# modbrainsv0_4_1.net
KiCad netlist of a schematic drawn in EAGLE
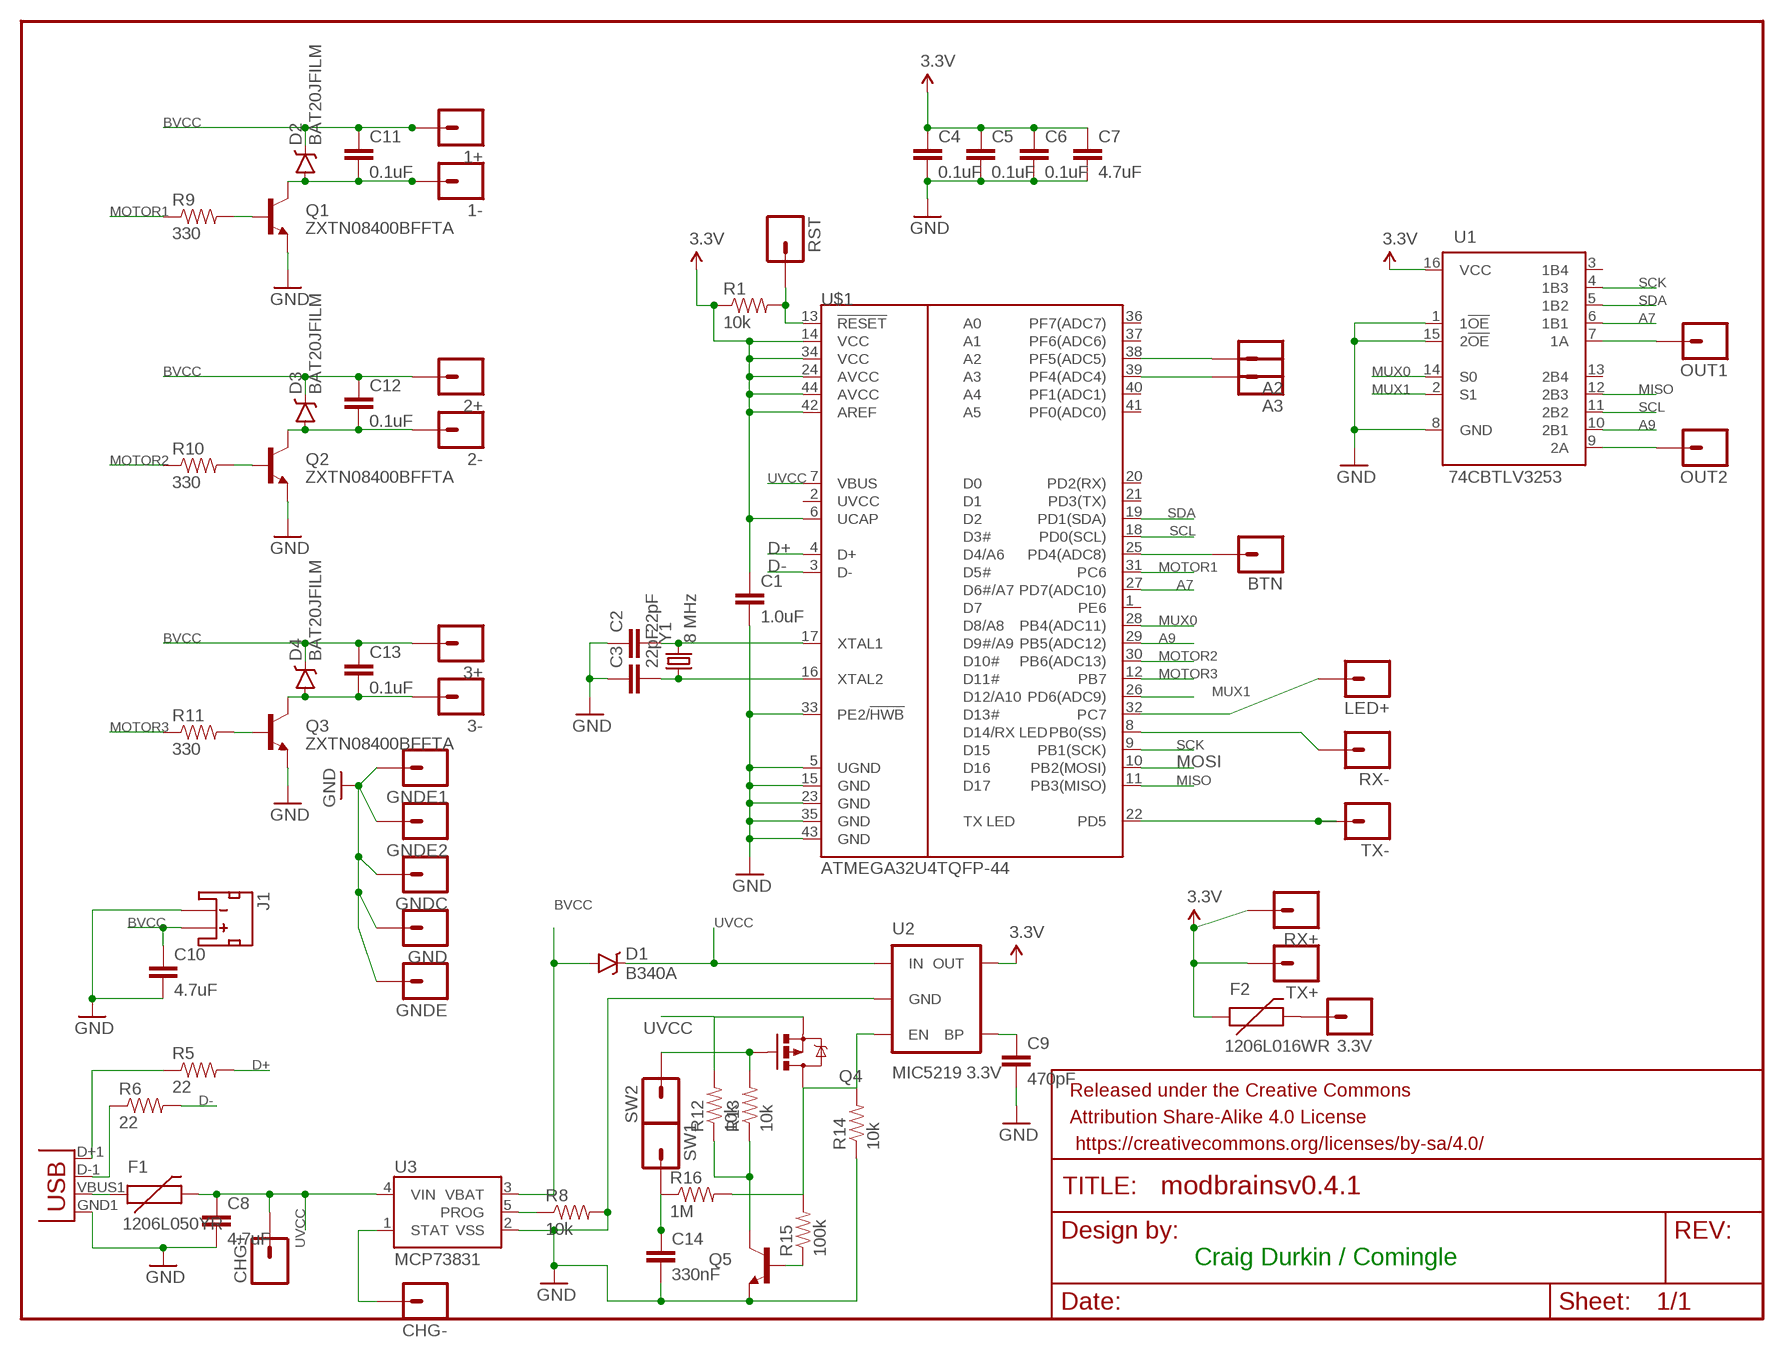
[diagram p0: schematic, sheet 1]

(export (version "E")
  (design (tool "Eeschema 10.0.6"))
  (components
    (comp (ref "1+")
      (value "M01PTH")
      (footprint "eagle-import:1X01")
      (libsource (lib "eagle-import") (part "M01PTH"))
    )
    (comp (ref "1-")
      (value "M01PTH")
      (footprint "eagle-import:1X01")
      (libsource (lib "eagle-import") (part "M01PTH"))
    )
    (comp (ref "2+")
      (value "M01PTH")
      (footprint "eagle-import:1X01")
      (libsource (lib "eagle-import") (part "M01PTH"))
    )
    (comp (ref "2-")
      (value "M01PTH")
      (footprint "eagle-import:1X01")
      (libsource (lib "eagle-import") (part "M01PTH"))
    )
    (comp (ref "3+")
      (value "M01PTH")
      (footprint "eagle-import:1X01")
      (libsource (lib "eagle-import") (part "M01PTH"))
    )
    (comp (ref "3-")
      (value "M01PTH")
      (footprint "eagle-import:1X01")
      (libsource (lib "eagle-import") (part "M01PTH"))
    )
    (comp (ref "3.3V")
      (value "M01PTH")
      (footprint "eagle-import:1X01")
      (libsource (lib "eagle-import") (part "M01PTH"))
    )
    (comp (ref "A2")
      (value "M01PTH")
      (footprint "eagle-import:1X01")
      (libsource (lib "eagle-import") (part "M01PTH"))
    )
    (comp (ref "A3")
      (value "M01PTH")
      (footprint "eagle-import:1X01")
      (libsource (lib "eagle-import") (part "M01PTH"))
    )
    (comp (ref "BTN")
      (value "M01PTH")
      (footprint "eagle-import:1X01")
      (libsource (lib "eagle-import") (part "M01PTH"))
    )
    (comp (ref "C1")
      (value "1.0uF")
      (footprint "eagle-import:0603-CAP")
      (libsource (lib "eagle-import") (part "CAP0603-CAP"))
    )
    (comp (ref "C2")
      (value "22pF")
      (footprint "eagle-import:0603-CAP")
      (libsource (lib "eagle-import") (part "CAP0603-CAP"))
    )
    (comp (ref "C3")
      (value "22pF")
      (footprint "eagle-import:0603-CAP")
      (libsource (lib "eagle-import") (part "CAP0603-CAP"))
    )
    (comp (ref "C4")
      (value "0.1uF")
      (footprint "eagle-import:0603-CAP")
      (libsource (lib "eagle-import") (part "SparkFun-Passives_CAP0603-CAP"))
    )
    (comp (ref "C5")
      (value "0.1uF")
      (footprint "eagle-import:0603-CAP")
      (libsource (lib "eagle-import") (part "SparkFun-Passives_CAP0603-CAP"))
    )
    (comp (ref "C6")
      (value "0.1uF")
      (footprint "eagle-import:0603-CAP")
      (libsource (lib "eagle-import") (part "SparkFun-Passives_CAP0603-CAP"))
    )
    (comp (ref "C7")
      (value "4.7uF")
      (footprint "eagle-import:0603-CAP")
      (libsource (lib "eagle-import") (part "SparkFun-Passives_CAP0603-CAP"))
    )
    (comp (ref "C8")
      (value "4.7uF")
      (footprint "eagle-import:1206")
      (libsource (lib "eagle-import") (part "SparkFun-Passives_CAP1206"))
    )
    (comp (ref "C9")
      (value "470pF")
      (footprint "eagle-import:0603-CAP")
      (libsource (lib "eagle-import") (part "CAP0603-CAP"))
    )
    (comp (ref "C10")
      (value "4.7uF")
      (footprint "eagle-import:1206")
      (libsource (lib "eagle-import") (part "SparkFun-Passives_CAP1206"))
    )
    (comp (ref "C11")
      (value "0.1uF")
      (footprint "eagle-import:0603-CAP")
      (libsource (lib "eagle-import") (part "CAP0603-CAP"))
    )
    (comp (ref "C12")
      (value "0.1uF")
      (footprint "eagle-import:0603-CAP")
      (libsource (lib "eagle-import") (part "CAP0603-CAP"))
    )
    (comp (ref "C13")
      (value "0.1uF")
      (footprint "eagle-import:0603-CAP")
      (libsource (lib "eagle-import") (part "CAP0603-CAP"))
    )
    (comp (ref "C14")
      (value "330nF")
      (footprint "eagle-import:0603-CAP")
      (libsource (lib "eagle-import") (part "CAP0603-CAP"))
    )
    (comp (ref "CHG+")
      (value "M01PTH")
      (footprint "eagle-import:1X01")
      (libsource (lib "eagle-import") (part "M01PTH"))
    )
    (comp (ref "CHG-")
      (value "M01PTH")
      (footprint "eagle-import:1X01")
      (libsource (lib "eagle-import") (part "M01PTH"))
    )
    (comp (ref "D1")
      (value "B340A")
      (footprint "eagle-import:SMA-DIODE")
      (libsource (lib "eagle-import") (part "DIODE-SCHOTTKY-B340A"))
    )
    (comp (ref "D2")
      (value "BAT20JFILM")
      (footprint "eagle-import:SOD-323")
      (libsource (lib "eagle-import") (part "BAT20JFILM"))
    )
    (comp (ref "D3")
      (value "BAT20JFILM")
      (footprint "eagle-import:SOD-323")
      (libsource (lib "eagle-import") (part "BAT20JFILM"))
    )
    (comp (ref "D4")
      (value "BAT20JFILM")
      (footprint "eagle-import:SOD-323")
      (libsource (lib "eagle-import") (part "BAT20JFILM"))
    )
    (comp (ref "F1")
      (value "1206L050YR")
      (footprint "eagle-import:PTC-1206")
      (libsource (lib "eagle-import") (part "PTCSMD"))
    )
    (comp (ref "F2")
      (value "1206L016WR")
      (footprint "eagle-import:PTC-1206")
      (libsource (lib "eagle-import") (part "PTCSMD"))
    )
    (comp (ref "FRAME1")
      (value "FRAME-LETTER")
      (footprint "eagle-import:CREATIVE_COMMONS")
      (libsource (lib "eagle-import") (part "FRAME-LETTER"))
    )
    (comp (ref "GND")
      (value "M01PTH")
      (footprint "eagle-import:1X01")
      (libsource (lib "eagle-import") (part "M01PTH"))
    )
    (comp (ref "GNDC")
      (value "M01PTH")
      (footprint "eagle-import:1X01")
      (libsource (lib "eagle-import") (part "M01PTH"))
    )
    (comp (ref "GNDE")
      (value "M01PTH")
      (footprint "eagle-import:1X01")
      (libsource (lib "eagle-import") (part "M01PTH"))
    )
    (comp (ref "GNDE1")
      (value "M01PTH")
      (footprint "eagle-import:1X01")
      (libsource (lib "eagle-import") (part "M01PTH"))
    )
    (comp (ref "GNDE2")
      (value "M01PTH")
      (footprint "eagle-import:1X01")
      (libsource (lib "eagle-import") (part "M01PTH"))
    )
    (comp (ref "J1")
      (value "JST_2MM_MALE")
      (footprint "eagle-import:JST-2-SMD")
      (libsource (lib "eagle-import") (part "JST_2MM_MALE"))
    )
    (comp (ref "JP4")
      (value "USB")
      (footprint "eagle-import:USB-B-MICRO-SMD_V03")
      (libsource (lib "eagle-import") (part "USB"))
    )
    (comp (ref "LED+")
      (value "M01PTH")
      (footprint "eagle-import:1X01")
      (libsource (lib "eagle-import") (part "M01PTH"))
    )
    (comp (ref "OUT1")
      (value "M01PTH")
      (footprint "eagle-import:1X01")
      (libsource (lib "eagle-import") (part "M01PTH"))
    )
    (comp (ref "OUT2")
      (value "M01PTH")
      (footprint "eagle-import:1X01")
      (libsource (lib "eagle-import") (part "M01PTH"))
    )
    (comp (ref "Q1")
      (value "ZXTN08400BFFTA")
      (footprint "eagle-import:SOT23-3")
      (libsource (lib "eagle-import") (part "TRANSISTOR_NPNSOT23-3"))
    )
    (comp (ref "Q2")
      (value "ZXTN08400BFFTA")
      (footprint "eagle-import:SOT23-3")
      (libsource (lib "eagle-import") (part "TRANSISTOR_NPNSOT23-3"))
    )
    (comp (ref "Q3")
      (value "ZXTN08400BFFTA")
      (footprint "eagle-import:SOT23-3")
      (libsource (lib "eagle-import") (part "TRANSISTOR_NPNSOT23-3"))
    )
    (comp (ref "Q4")
      (value "NTS2101PT1G")
      (footprint "eagle-import:SOT23-3")
      (libsource (lib "eagle-import") (part "MOSFET-PCHANNEL"))
    )
    (comp (ref "Q5")
      (value "MMBT2222A")
      (footprint "eagle-import:SOT23-3")
      (libsource (lib "eagle-import") (part "TRANSISTOR_NPNMMBT2222A"))
    )
    (comp (ref "R1")
      (value "10k")
      (footprint "eagle-import:0603-RES")
      (libsource (lib "eagle-import") (part "RESISTOR0603-RES"))
    )
    (comp (ref "R5")
      (value "22")
      (footprint "eagle-import:0603-RES")
      (libsource (lib "eagle-import") (part "RESISTOR0603-RES"))
    )
    (comp (ref "R6")
      (value "22")
      (footprint "eagle-import:0603-RES")
      (libsource (lib "eagle-import") (part "RESISTOR0603-RES"))
    )
    (comp (ref "R8")
      (value "10k")
      (footprint "eagle-import:0603-RES")
      (libsource (lib "eagle-import") (part "RESISTOR0603-RES"))
    )
    (comp (ref "R9")
      (value "330")
      (footprint "eagle-import:0603-RES")
      (libsource (lib "eagle-import") (part "RESISTOR0603-RES"))
    )
    (comp (ref "R10")
      (value "330")
      (footprint "eagle-import:0603-RES")
      (libsource (lib "eagle-import") (part "RESISTOR0603-RES"))
    )
    (comp (ref "R11")
      (value "330")
      (footprint "eagle-import:0603-RES")
      (libsource (lib "eagle-import") (part "RESISTOR0603-RES"))
    )
    (comp (ref "R12")
      (value "10k")
      (footprint "eagle-import:0603-RES")
      (libsource (lib "eagle-import") (part "RESISTOR0603-RES"))
    )
    (comp (ref "R13")
      (value "10k")
      (footprint "eagle-import:0603-RES")
      (libsource (lib "eagle-import") (part "RESISTOR0603-RES"))
    )
    (comp (ref "R14")
      (value "10k")
      (footprint "eagle-import:0603-RES")
      (libsource (lib "eagle-import") (part "RESISTOR0603-RES"))
    )
    (comp (ref "R15")
      (value "100k")
      (footprint "eagle-import:0603-RES")
      (libsource (lib "eagle-import") (part "RESISTOR0603-RES"))
    )
    (comp (ref "R16")
      (value "1M")
      (footprint "eagle-import:0603-RES")
      (libsource (lib "eagle-import") (part "RESISTOR0603-RES"))
    )
    (comp (ref "RST")
      (value "M01PTH")
      (footprint "eagle-import:1X01")
      (libsource (lib "eagle-import") (part "M01PTH"))
    )
    (comp (ref "RX+")
      (value "M01PTH")
      (footprint "eagle-import:1X01")
      (libsource (lib "eagle-import") (part "M01PTH"))
    )
    (comp (ref "RX-")
      (value "M01PTH")
      (footprint "eagle-import:1X01")
      (libsource (lib "eagle-import") (part "M01PTH"))
    )
    (comp (ref "SW1")
      (value "M01PTH")
      (footprint "eagle-import:1X01")
      (libsource (lib "eagle-import") (part "M01PTH"))
    )
    (comp (ref "SW2")
      (value "M01PTH")
      (footprint "eagle-import:1X01")
      (libsource (lib "eagle-import") (part "M01PTH"))
    )
    (comp (ref "TX+")
      (value "M01PTH")
      (footprint "eagle-import:1X01")
      (libsource (lib "eagle-import") (part "M01PTH"))
    )
    (comp (ref "TX-")
      (value "M01PTH")
      (footprint "eagle-import:1X01")
      (libsource (lib "eagle-import") (part "M01PTH"))
    )
    (comp (ref "U$1")
      (value "ATMEGA32U4TQFP-44")
      (footprint "eagle-import:TQFP44")
      (libsource (lib "eagle-import") (part "ATMEGA32U4TQFP-44"))
    )
    (comp (ref "U1")
      (value "74CBTLV3253")
      (footprint "eagle-import:SSOP16-PRACTICE")
      (libsource (lib "eagle-import") (part "74CBTLV3253"))
    )
    (comp (ref "U2")
      (value "MIC5219 3.3V")
      (footprint "eagle-import:SOT23-5")
      (libsource (lib "eagle-import") (part "V_REG_MIC52193.3V"))
    )
    (comp (ref "U3")
      (value "MCP73831")
      (footprint "eagle-import:SOT23-5")
      (libsource (lib "eagle-import") (part "MCP73831"))
    )
    (comp (ref "Y1")
      (value "8 MHz")
      (footprint "eagle-import:CRYSTAL-SMD-5X3")
      (libsource (lib "eagle-import") (part "CRYSTAL5X3"))
    )
  )
  (nets
    (net (code "1") (name "/A7") (class "Default")
      (node (ref "U$1") (pin "27") (pinfunction "PD7(ADC10)_27") (pintype "bidirectional"))
      (node (ref "U1") (pin "6") (pinfunction "1B1_6") (pintype "bidirectional"))
    )
    (net (code "2") (name "/A9") (class "Default")
      (node (ref "U$1") (pin "29") (pinfunction "PB5(ADC12)_29") (pintype "bidirectional"))
      (node (ref "U1") (pin "10") (pinfunction "2B1_10") (pintype "bidirectional"))
    )
    (net (code "3") (name "/BVCC") (class "Default")
      (node (ref "1+") (pin "1") (pinfunction "1_1") (pintype "passive"))
      (node (ref "2+") (pin "1") (pinfunction "1_1") (pintype "passive"))
      (node (ref "3+") (pin "1") (pinfunction "1_1") (pintype "passive"))
      (node (ref "C10") (pin "1") (pinfunction "1_1") (pintype "passive"))
      (node (ref "C11") (pin "1") (pinfunction "1_1") (pintype "passive"))
      (node (ref "C12") (pin "1") (pinfunction "1_1") (pintype "passive"))
      (node (ref "C13") (pin "1") (pinfunction "1_1") (pintype "passive"))
      (node (ref "D1") (pin "A") (pinfunction "A_A") (pintype "passive"))
      (node (ref "D2") (pin "C") (pinfunction "C_C") (pintype "passive"))
      (node (ref "D3") (pin "C") (pinfunction "C_C") (pintype "passive"))
      (node (ref "D4") (pin "C") (pinfunction "C_C") (pintype "passive"))
      (node (ref "J1") (pin "2") (pinfunction "+_2") (pintype "bidirectional"))
      (node (ref "U3") (pin "3") (pinfunction "VBAT_3") (pintype "power_in"))
    )
    (net (code "4") (name "/D+") (class "Default")
      (node (ref "R5") (pin "2") (pinfunction "2_2") (pintype "passive"))
      (node (ref "U$1") (pin "4") (pinfunction "D+_4") (pintype "bidirectional"))
    )
    (net (code "5") (name "/D-") (class "Default")
      (node (ref "R6") (pin "2") (pinfunction "2_2") (pintype "passive"))
      (node (ref "U$1") (pin "3") (pinfunction "D-_3") (pintype "bidirectional"))
    )
    (net (code "6") (name "/MISO") (class "Default")
      (node (ref "U$1") (pin "11") (pinfunction "PB3(MISO)_11") (pintype "bidirectional"))
      (node (ref "U1") (pin "12") (pinfunction "2B3_12") (pintype "bidirectional"))
    )
    (net (code "7") (name "/MOSI") (class "Default")
      (node (ref "U$1") (pin "10") (pinfunction "PB2(MOSI)_10") (pintype "bidirectional"))
    )
    (net (code "8") (name "/MOTOR1") (class "Default")
      (node (ref "R9") (pin "1") (pinfunction "1_1") (pintype "passive"))
      (node (ref "U$1") (pin "31") (pinfunction "PC6_31") (pintype "bidirectional"))
    )
    (net (code "9") (name "/MOTOR2") (class "Default")
      (node (ref "R10") (pin "1") (pinfunction "1_1") (pintype "passive"))
      (node (ref "U$1") (pin "30") (pinfunction "PB6(ADC13)_30") (pintype "bidirectional"))
    )
    (net (code "10") (name "/MOTOR3") (class "Default")
      (node (ref "R11") (pin "1") (pinfunction "1_1") (pintype "passive"))
      (node (ref "U$1") (pin "12") (pinfunction "PB7_12") (pintype "bidirectional"))
    )
    (net (code "11") (name "/MUX0") (class "Default")
      (node (ref "U$1") (pin "28") (pinfunction "PB4(ADC11)_28") (pintype "bidirectional"))
      (node (ref "U1") (pin "14") (pinfunction "S0_14") (pintype "bidirectional"))
    )
    (net (code "12") (name "/MUX1") (class "Default")
      (node (ref "U$1") (pin "26") (pinfunction "PD6(ADC9)_26") (pintype "bidirectional"))
      (node (ref "U1") (pin "2") (pinfunction "S1_2") (pintype "bidirectional"))
    )
    (net (code "13") (name "/SCK") (class "Default")
      (node (ref "U$1") (pin "9") (pinfunction "PB1(SCK)_9") (pintype "bidirectional"))
      (node (ref "U1") (pin "4") (pinfunction "1B3_4") (pintype "bidirectional"))
    )
    (net (code "14") (name "/SCL") (class "Default")
      (node (ref "U$1") (pin "18") (pinfunction "PD0(SCL)_18") (pintype "bidirectional"))
      (node (ref "U1") (pin "11") (pinfunction "2B2_11") (pintype "bidirectional"))
    )
    (net (code "15") (name "/SDA") (class "Default")
      (node (ref "U$1") (pin "19") (pinfunction "PD1(SDA)_19") (pintype "bidirectional"))
      (node (ref "U1") (pin "5") (pinfunction "1B2_5") (pintype "bidirectional"))
    )
    (net (code "16") (name "/UVCC") (class "Default")
      (node (ref "C8") (pin "1") (pinfunction "1_1") (pintype "passive"))
      (node (ref "CHG+") (pin "1") (pinfunction "1_1") (pintype "passive"))
      (node (ref "D1") (pin "C") (pinfunction "C_C") (pintype "passive"))
      (node (ref "F1") (pin "2") (pinfunction "2_2") (pintype "bidirectional"))
      (node (ref "Q4") (pin "2") (pinfunction "S_2") (pintype "passive"))
      (node (ref "R12") (pin "2") (pinfunction "2_2") (pintype "passive"))
      (node (ref "U$1") (pin "7") (pinfunction "VBUS_7") (pintype "bidirectional"))
      (node (ref "U2") (pin "1") (pinfunction "IN_1") (pintype "input"))
      (node (ref "U3") (pin "4") (pinfunction "VIN_4") (pintype "power_in"))
    )
    (net (code "17") (name "3.3V") (class "Default")
      (node (ref "C1") (pin "1") (pinfunction "1_1") (pintype "passive"))
      (node (ref "C4") (pin "1") (pinfunction "1_1") (pintype "passive"))
      (node (ref "C5") (pin "1") (pinfunction "1_1") (pintype "passive"))
      (node (ref "C6") (pin "1") (pinfunction "1_1") (pintype "passive"))
      (node (ref "C7") (pin "1") (pinfunction "1_1") (pintype "passive"))
      (node (ref "F2") (pin "1") (pinfunction "1_1") (pintype "bidirectional"))
      (node (ref "R1") (pin "1") (pinfunction "1_1") (pintype "passive"))
      (node (ref "RX+") (pin "1") (pinfunction "1_1") (pintype "passive"))
      (node (ref "TX+") (pin "1") (pinfunction "1_1") (pintype "passive"))
      (node (ref "U$1") (pin "14") (pinfunction "VCC_14") (pintype "bidirectional"))
      (node (ref "U$1") (pin "24") (pinfunction "AVCC_24") (pintype "bidirectional"))
      (node (ref "U$1") (pin "34") (pinfunction "VCC_34") (pintype "bidirectional"))
      (node (ref "U$1") (pin "42") (pinfunction "AREF_42") (pintype "bidirectional"))
      (node (ref "U$1") (pin "44") (pinfunction "AVCC_44") (pintype "bidirectional"))
      (node (ref "U$1") (pin "6") (pinfunction "UCAP_6") (pintype "bidirectional"))
      (node (ref "U1") (pin "16") (pinfunction "VCC_16") (pintype "power_in"))
      (node (ref "U2") (pin "5") (pinfunction "OUT_5") (pintype "passive"))
    )
    (net (code "18") (name "GND") (class "Default")
      (node (ref "C1") (pin "2") (pinfunction "2_2") (pintype "passive"))
      (node (ref "C10") (pin "2") (pinfunction "2_2") (pintype "passive"))
      (node (ref "C14") (pin "2") (pinfunction "2_2") (pintype "passive"))
      (node (ref "C2") (pin "1") (pinfunction "1_1") (pintype "passive"))
      (node (ref "C3") (pin "1") (pinfunction "1_1") (pintype "passive"))
      (node (ref "C4") (pin "2") (pinfunction "2_2") (pintype "passive"))
      (node (ref "C5") (pin "2") (pinfunction "2_2") (pintype "passive"))
      (node (ref "C6") (pin "2") (pinfunction "2_2") (pintype "passive"))
      (node (ref "C7") (pin "2") (pinfunction "2_2") (pintype "passive"))
      (node (ref "C8") (pin "2") (pinfunction "2_2") (pintype "passive"))
      (node (ref "C9") (pin "2") (pinfunction "2_2") (pintype "passive"))
      (node (ref "GND") (pin "1") (pinfunction "1_1") (pintype "passive"))
      (node (ref "GNDC") (pin "1") (pinfunction "1_1") (pintype "passive"))
      (node (ref "GNDE") (pin "1") (pinfunction "1_1") (pintype "passive"))
      (node (ref "GNDE1") (pin "1") (pinfunction "1_1") (pintype "passive"))
      (node (ref "GNDE2") (pin "1") (pinfunction "1_1") (pintype "passive"))
      (node (ref "J1") (pin "1") (pinfunction "-_1") (pintype "bidirectional"))
      (node (ref "JP4") (pin "GND1") (pinfunction "GND_GND1") (pintype "bidirectional"))
      (node (ref "Q1") (pin "2") (pinfunction "E_2") (pintype "passive"))
      (node (ref "Q2") (pin "2") (pinfunction "E_2") (pintype "passive"))
      (node (ref "Q3") (pin "2") (pinfunction "E_2") (pintype "passive"))
      (node (ref "Q5") (pin "2") (pinfunction "E_2") (pintype "passive"))
      (node (ref "R14") (pin "1") (pinfunction "1_1") (pintype "passive"))
      (node (ref "R8") (pin "2") (pinfunction "2_2") (pintype "passive"))
      (node (ref "U$1") (pin "15") (pinfunction "GND_15") (pintype "bidirectional"))
      (node (ref "U$1") (pin "23") (pinfunction "GND_23") (pintype "bidirectional"))
      (node (ref "U$1") (pin "33") (pinfunction "PE2/~{HWB}_33") (pintype "bidirectional"))
      (node (ref "U$1") (pin "35") (pinfunction "GND_35") (pintype "bidirectional"))
      (node (ref "U$1") (pin "43") (pinfunction "GND_43") (pintype "bidirectional"))
      (node (ref "U$1") (pin "5") (pinfunction "UGND_5") (pintype "bidirectional"))
      (node (ref "U1") (pin "1") (pinfunction "1~{OE}_1") (pintype "input"))
      (node (ref "U1") (pin "15") (pinfunction "2~{OE}_15") (pintype "input"))
      (node (ref "U1") (pin "8") (pinfunction "GND_8") (pintype "power_in"))
      (node (ref "U2") (pin "2") (pinfunction "GND_2") (pintype "input"))
      (node (ref "U3") (pin "2") (pinfunction "VSS_2") (pintype "power_in"))
    )
    (net (code "19") (name "Net-(3.3V-Pad1)") (class "Default")
      (node (ref "3.3V") (pin "1") (pinfunction "1_1") (pintype "passive"))
      (node (ref "F2") (pin "2") (pinfunction "2_2") (pintype "bidirectional"))
    )
    (net (code "20") (name "Net-(C14-Pad1)") (class "Default")
      (node (ref "C14") (pin "1") (pinfunction "1_1") (pintype "passive"))
      (node (ref "R16") (pin "1") (pinfunction "1_1") (pintype "passive"))
      (node (ref "SW1") (pin "1") (pinfunction "1_1") (pintype "passive"))
    )
    (net (code "21") (name "Net-(JP4-D+)") (class "Default")
      (node (ref "JP4") (pin "D+1") (pinfunction "D+_D+1") (pintype "bidirectional"))
      (node (ref "R5") (pin "1") (pinfunction "1_1") (pintype "passive"))
    )
    (net (code "22") (name "Net-(JP4-D-)") (class "Default")
      (node (ref "JP4") (pin "D-1") (pinfunction "D-_D-1") (pintype "bidirectional"))
      (node (ref "R6") (pin "1") (pinfunction "1_1") (pintype "passive"))
    )
    (net (code "23") (name "Net-(JP4-VBUS)") (class "Default")
      (node (ref "F1") (pin "1") (pinfunction "1_1") (pintype "bidirectional"))
      (node (ref "JP4") (pin "VBUS1") (pinfunction "VBUS_VBUS1") (pintype "bidirectional"))
    )
    (net (code "24") (name "Net-(Q1-B)") (class "Default")
      (node (ref "Q1") (pin "1") (pinfunction "B_1") (pintype "passive"))
      (node (ref "R9") (pin "2") (pinfunction "2_2") (pintype "passive"))
    )
    (net (code "25") (name "Net-(Q1-C)") (class "Default")
      (node (ref "1-") (pin "1") (pinfunction "1_1") (pintype "passive"))
      (node (ref "C11") (pin "2") (pinfunction "2_2") (pintype "passive"))
      (node (ref "D2") (pin "A") (pinfunction "A_A") (pintype "passive"))
      (node (ref "Q1") (pin "3") (pinfunction "C_3") (pintype "passive"))
    )
    (net (code "26") (name "Net-(Q2-B)") (class "Default")
      (node (ref "Q2") (pin "1") (pinfunction "B_1") (pintype "passive"))
      (node (ref "R10") (pin "2") (pinfunction "2_2") (pintype "passive"))
    )
    (net (code "27") (name "Net-(Q2-C)") (class "Default")
      (node (ref "2-") (pin "1") (pinfunction "1_1") (pintype "passive"))
      (node (ref "C12") (pin "2") (pinfunction "2_2") (pintype "passive"))
      (node (ref "D3") (pin "A") (pinfunction "A_A") (pintype "passive"))
      (node (ref "Q2") (pin "3") (pinfunction "C_3") (pintype "passive"))
    )
    (net (code "28") (name "Net-(Q3-B)") (class "Default")
      (node (ref "Q3") (pin "1") (pinfunction "B_1") (pintype "passive"))
      (node (ref "R11") (pin "2") (pinfunction "2_2") (pintype "passive"))
    )
    (net (code "29") (name "Net-(Q3-C)") (class "Default")
      (node (ref "3-") (pin "1") (pinfunction "1_1") (pintype "passive"))
      (node (ref "C13") (pin "2") (pinfunction "2_2") (pintype "passive"))
      (node (ref "D4") (pin "A") (pinfunction "A_A") (pintype "passive"))
      (node (ref "Q3") (pin "3") (pinfunction "C_3") (pintype "passive"))
    )
    (net (code "30") (name "Net-(Q4-D)") (class "Default")
      (node (ref "Q4") (pin "3") (pinfunction "D_3") (pintype "passive"))
      (node (ref "R14") (pin "2") (pinfunction "2_2") (pintype "passive"))
      (node (ref "R15") (pin "2") (pinfunction "2_2") (pintype "passive"))
      (node (ref "R16") (pin "2") (pinfunction "2_2") (pintype "passive"))
      (node (ref "U2") (pin "3") (pinfunction "EN_3") (pintype "input"))
    )
    (net (code "31") (name "Net-(Q4-G)") (class "Default")
      (node (ref "Q4") (pin "1") (pinfunction "G_1") (pintype "passive"))
      (node (ref "R13") (pin "2") (pinfunction "2_2") (pintype "passive"))
      (node (ref "SW2") (pin "1") (pinfunction "1_1") (pintype "passive"))
    )
    (net (code "32") (name "Net-(Q5-B)") (class "Default")
      (node (ref "Q5") (pin "1") (pinfunction "B_1") (pintype "passive"))
      (node (ref "R15") (pin "1") (pinfunction "1_1") (pintype "passive"))
    )
    (net (code "33") (name "Net-(Q5-C)") (class "Default")
      (node (ref "Q5") (pin "3") (pinfunction "C_3") (pintype "passive"))
      (node (ref "R12") (pin "1") (pinfunction "1_1") (pintype "passive"))
      (node (ref "R13") (pin "1") (pinfunction "1_1") (pintype "passive"))
    )
    (net (code "34") (name "Net-(U$1-PB0(SS))") (class "Default")
      (node (ref "RX-") (pin "1") (pinfunction "1_1") (pintype "passive"))
      (node (ref "U$1") (pin "8") (pinfunction "PB0(SS)_8") (pintype "bidirectional"))
    )
    (net (code "35") (name "Net-(U$1-PC7)") (class "Default")
      (node (ref "LED+") (pin "1") (pinfunction "1_1") (pintype "passive"))
      (node (ref "U$1") (pin "32") (pinfunction "PC7_32") (pintype "bidirectional"))
    )
    (net (code "36") (name "Net-(U$1-PD4(ADC8))") (class "Default")
      (node (ref "BTN") (pin "1") (pinfunction "1_1") (pintype "passive"))
      (node (ref "U$1") (pin "25") (pinfunction "PD4(ADC8)_25") (pintype "bidirectional"))
    )
    (net (code "37") (name "Net-(U$1-PD5)") (class "Default")
      (node (ref "TX-") (pin "1") (pinfunction "1_1") (pintype "passive"))
      (node (ref "U$1") (pin "22") (pinfunction "PD5_22") (pintype "bidirectional"))
    )
    (net (code "38") (name "Net-(U$1-PF4(ADC4))") (class "Default")
      (node (ref "A3") (pin "1") (pinfunction "1_1") (pintype "passive"))
      (node (ref "U$1") (pin "39") (pinfunction "PF4(ADC4)_39") (pintype "bidirectional"))
    )
    (net (code "39") (name "Net-(U$1-PF5(ADC5))") (class "Default")
      (node (ref "A2") (pin "1") (pinfunction "1_1") (pintype "passive"))
      (node (ref "U$1") (pin "38") (pinfunction "PF5(ADC5)_38") (pintype "bidirectional"))
    )
    (net (code "40") (name "Net-(U$1-XTAL1)") (class "Default")
      (node (ref "C2") (pin "2") (pinfunction "2_2") (pintype "passive"))
      (node (ref "U$1") (pin "17") (pinfunction "XTAL1_17") (pintype "bidirectional"))
      (node (ref "Y1") (pin "3") (pinfunction "2_3") (pintype "passive"))
    )
    (net (code "41") (name "Net-(U$1-XTAL2)") (class "Default")
      (node (ref "C3") (pin "2") (pinfunction "2_2") (pintype "passive"))
      (node (ref "U$1") (pin "16") (pinfunction "XTAL2_16") (pintype "bidirectional"))
      (node (ref "Y1") (pin "1") (pinfunction "1_1") (pintype "passive"))
    )
    (net (code "42") (name "Net-(U$1-~{RESET})") (class "Default")
      (node (ref "R1") (pin "2") (pinfunction "2_2") (pintype "passive"))
      (node (ref "RST") (pin "1") (pinfunction "1_1") (pintype "passive"))
      (node (ref "U$1") (pin "13") (pinfunction "~{RESET}_13") (pintype "bidirectional"))
    )
    (net (code "43") (name "Net-(U1-1A)") (class "Default")
      (node (ref "OUT1") (pin "1") (pinfunction "1_1") (pintype "passive"))
      (node (ref "U1") (pin "7") (pinfunction "1A_7") (pintype "bidirectional"))
    )
    (net (code "44") (name "Net-(U1-2A)") (class "Default")
      (node (ref "OUT2") (pin "1") (pinfunction "1_1") (pintype "passive"))
      (node (ref "U1") (pin "9") (pinfunction "2A_9") (pintype "bidirectional"))
    )
    (net (code "45") (name "Net-(U2-BP)") (class "Default")
      (node (ref "C9") (pin "1") (pinfunction "1_1") (pintype "passive"))
      (node (ref "U2") (pin "4") (pinfunction "BP_4") (pintype "input"))
    )
    (net (code "46") (name "Net-(U3-PROG)") (class "Default")
      (node (ref "R8") (pin "1") (pinfunction "1_1") (pintype "passive"))
      (node (ref "U3") (pin "5") (pinfunction "PROG_5") (pintype "bidirectional"))
    )
    (net (code "47") (name "Net-(U3-STAT)") (class "Default")
      (node (ref "CHG-") (pin "1") (pinfunction "1_1") (pintype "passive"))
      (node (ref "U3") (pin "1") (pinfunction "STAT_1") (pintype "output"))
    )
    (net (code "48") (name "unconnected-(J1-PAD1-PadNC1)") (class "Default")
      (node (ref "J1") (pin "NC1") (pinfunction "PAD1_NC1") (pintype "bidirectional"))
    )
    (net (code "49") (name "unconnected-(J1-PAD2-PadNC2)") (class "Default")
      (node (ref "J1") (pin "NC2") (pinfunction "PAD2_NC2") (pintype "bidirectional"))
    )
    (net (code "50") (name "unconnected-(U$1-PD2(RX)-Pad20)") (class "Default")
      (node (ref "U$1") (pin "20") (pinfunction "PD2(RX)_20") (pintype "bidirectional"))
    )
    (net (code "51") (name "unconnected-(U$1-PD3(TX)-Pad21)") (class "Default")
      (node (ref "U$1") (pin "21") (pinfunction "PD3(TX)_21") (pintype "bidirectional"))
    )
    (net (code "52") (name "unconnected-(U$1-PE6-Pad1)") (class "Default")
      (node (ref "U$1") (pin "1") (pinfunction "PE6_1") (pintype "bidirectional"))
    )
    (net (code "53") (name "unconnected-(U$1-PF0(ADC0)-Pad41)") (class "Default")
      (node (ref "U$1") (pin "41") (pinfunction "PF0(ADC0)_41") (pintype "bidirectional"))
    )
    (net (code "54") (name "unconnected-(U$1-PF1(ADC1)-Pad40)") (class "Default")
      (node (ref "U$1") (pin "40") (pinfunction "PF1(ADC1)_40") (pintype "bidirectional"))
    )
    (net (code "55") (name "unconnected-(U$1-PF6(ADC6)-Pad37)") (class "Default")
      (node (ref "U$1") (pin "37") (pinfunction "PF6(ADC6)_37") (pintype "bidirectional"))
    )
    (net (code "56") (name "unconnected-(U$1-PF7(ADC7)-Pad36)") (class "Default")
      (node (ref "U$1") (pin "36") (pinfunction "PF7(ADC7)_36") (pintype "bidirectional"))
    )
    (net (code "57") (name "unconnected-(U$1-UVCC-Pad2)") (class "Default")
      (node (ref "U$1") (pin "2") (pinfunction "UVCC_2") (pintype "bidirectional"))
    )
    (net (code "58") (name "unconnected-(U1-1B4-Pad3)") (class "Default")
      (node (ref "U1") (pin "3") (pinfunction "1B4_3") (pintype "bidirectional"))
    )
    (net (code "59") (name "unconnected-(U1-2B4-Pad13)") (class "Default")
      (node (ref "U1") (pin "13") (pinfunction "2B4_13") (pintype "bidirectional"))
    )
  )
)
